# Bauble.net
KiCad netlist of a schematic drawn in EAGLE
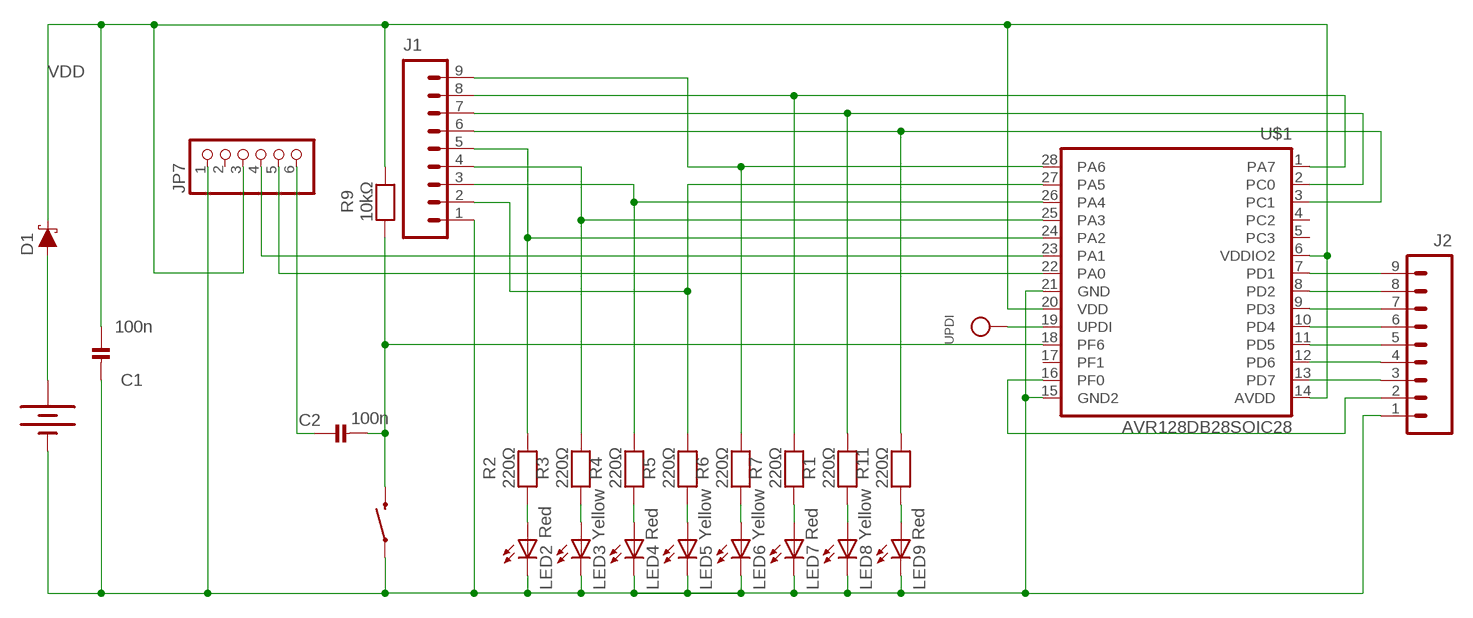
[diagram p0: schematic, sheet 1]

(export (version "E")
  (design (tool "Eeschema 10.0.6"))
  (components
    (comp (ref "BAT2")
      (value "20mm coincell")
      (footprint "eagle-import:BATTCON_20MM_4LEGS")
      (libsource (lib "eagle-import") (part "BATTERY20MM_4LEGS"))
    )
    (comp (ref "C1")
      (value "100n")
      (footprint "eagle-import:_0805MP")
      (libsource (lib "eagle-import") (part "CAP_CERAMIC_0805MP"))
    )
    (comp (ref "C2")
      (value "100n")
      (footprint "eagle-import:_0805MP")
      (libsource (lib "eagle-import") (part "CAP_CERAMIC_0805MP"))
    )
    (comp (ref "D1")
      (value "3A/10V/280mV")
      (footprint "eagle-import:SOD-323")
      (libsource (lib "eagle-import") (part "DIODE-SCHOTTKY-BAT60A"))
    )
    (comp (ref "J1")
      (value "M82MM")
      (footprint "eagle-import:1X10-2MM")
      (libsource (lib "eagle-import") (part "M82MM"))
    )
    (comp (ref "J2")
      (value "M82MM")
      (footprint "eagle-import:1X10-2MM")
      (libsource (lib "eagle-import") (part "M82MM"))
    )
    (comp (ref "JP7")
      (value "HEADER-1X6ROUND")
      (footprint "eagle-import:1X06_ROUND")
      (libsource (lib "eagle-import") (part "HEADER-1X6ROUND"))
    )
    (comp (ref "LED2")
      (value "Red")
      (footprint "eagle-import:CHIPLED_0805")
      (libsource (lib "eagle-import") (part "LEDCHIPLED_0805"))
    )
    (comp (ref "LED3")
      (value "Yellow")
      (footprint "eagle-import:CHIPLED_0805")
      (libsource (lib "eagle-import") (part "LEDCHIPLED_0805"))
    )
    (comp (ref "LED4")
      (value "Red")
      (footprint "eagle-import:CHIPLED_0805")
      (libsource (lib "eagle-import") (part "LEDCHIPLED_0805"))
    )
    (comp (ref "LED5")
      (value "Yellow")
      (footprint "eagle-import:CHIPLED_0805")
      (libsource (lib "eagle-import") (part "LEDCHIPLED_0805"))
    )
    (comp (ref "LED6")
      (value "Yellow")
      (footprint "eagle-import:CHIPLED_0805")
      (libsource (lib "eagle-import") (part "LEDCHIPLED_0805"))
    )
    (comp (ref "LED7")
      (value "Red")
      (footprint "eagle-import:CHIPLED_0805")
      (libsource (lib "eagle-import") (part "LEDCHIPLED_0805"))
    )
    (comp (ref "LED8")
      (value "Yellow")
      (footprint "eagle-import:CHIPLED_0805")
      (libsource (lib "eagle-import") (part "LEDCHIPLED_0805"))
    )
    (comp (ref "LED9")
      (value "Red")
      (footprint "eagle-import:CHIPLED_0805")
      (libsource (lib "eagle-import") (part "LEDCHIPLED_0805"))
    )
    (comp (ref "R1")
      (value "220Ω")
      (footprint "eagle-import:_0805MP")
      (libsource (lib "eagle-import") (part "RESISTOR_0805MP"))
    )
    (comp (ref "R2")
      (value "220Ω")
      (footprint "eagle-import:_0805MP")
      (libsource (lib "eagle-import") (part "RESISTOR_0805MP"))
    )
    (comp (ref "R3")
      (value "220Ω")
      (footprint "eagle-import:_0805MP")
      (libsource (lib "eagle-import") (part "RESISTOR_0805MP"))
    )
    (comp (ref "R4")
      (value "220Ω")
      (footprint "eagle-import:_0805MP")
      (libsource (lib "eagle-import") (part "RESISTOR_0805MP"))
    )
    (comp (ref "R5")
      (value "220Ω")
      (footprint "eagle-import:_0805MP")
      (libsource (lib "eagle-import") (part "RESISTOR_0805MP"))
    )
    (comp (ref "R6")
      (value "220Ω")
      (footprint "eagle-import:_0805MP")
      (libsource (lib "eagle-import") (part "RESISTOR_0805MP"))
    )
    (comp (ref "R7")
      (value "220Ω")
      (footprint "eagle-import:_0805MP")
      (libsource (lib "eagle-import") (part "RESISTOR_0805MP"))
    )
    (comp (ref "R9")
      (value "10kΩ")
      (footprint "eagle-import:_0805MP")
      (libsource (lib "eagle-import") (part "RESISTOR_0805MP"))
    )
    (comp (ref "R11")
      (value "220Ω")
      (footprint "eagle-import:_0805MP")
      (libsource (lib "eagle-import") (part "RESISTOR_0805MP"))
    )
    (comp (ref "S2")
      (value "SWITCH-MOMENTARY-2SMD")
      (footprint "eagle-import:TACTILE-SWITCH-SMD")
      (libsource (lib "eagle-import") (part "SWITCH-MOMENTARY-2SMD"))
    )
    (comp (ref "U$1")
      (value "AVR128DB28SOIC28")
      (footprint "eagle-import:SO-28W")
      (libsource (lib "eagle-import") (part "AVR128DB28SOIC28"))
    )
    (comp (ref "UPDI")
      (value "TESTPOINTROUND1MM")
      (footprint "eagle-import:TESTPOINT_ROUND_1MM")
      (libsource (lib "eagle-import") (part "TESTPOINTROUND1MM"))
    )
  )
  (nets
    (net (code "1") (name "Net-(BAT2-+-PadPOSITIVE@1)") (class "Default")
      (node (ref "BAT2") (pin "POSITIVE@1") (pinfunction "+_POSITIVE@1") (pintype "power_in"))
      (node (ref "BAT2") (pin "POSITIVE@2") (pinfunction "+_POSITIVE@2") (pintype "power_in"))
      (node (ref "BAT2") (pin "POSITIVE@3") (pinfunction "+_POSITIVE@3") (pintype "power_in"))
      (node (ref "BAT2") (pin "POSITIVE@4") (pinfunction "+_POSITIVE@4") (pintype "power_in"))
      (node (ref "D1") (pin "A") (pinfunction "A_A") (pintype "passive"))
    )
    (net (code "2") (name "Net-(BAT2--)") (class "Default")
      (node (ref "BAT2") (pin "NEGATIVE") (pinfunction "-_NEGATIVE") (pintype "power_in"))
      (node (ref "C1") (pin "2") (pinfunction "P$2_2") (pintype "passive"))
      (node (ref "J1") (pin "1") (pinfunction "1_1") (pintype "passive"))
      (node (ref "J2") (pin "1") (pinfunction "1_1") (pintype "passive"))
      (node (ref "JP7") (pin "1") (pinfunction "1_1") (pintype "passive"))
      (node (ref "LED2") (pin "C") (pinfunction "C_C") (pintype "passive"))
      (node (ref "LED3") (pin "C") (pinfunction "C_C") (pintype "passive"))
      (node (ref "LED4") (pin "C") (pinfunction "C_C") (pintype "passive"))
      (node (ref "LED5") (pin "C") (pinfunction "C_C") (pintype "passive"))
      (node (ref "LED6") (pin "C") (pinfunction "C_C") (pintype "passive"))
      (node (ref "LED7") (pin "C") (pinfunction "C_C") (pintype "passive"))
      (node (ref "LED8") (pin "C") (pinfunction "C_C") (pintype "passive"))
      (node (ref "LED9") (pin "C") (pinfunction "C_C") (pintype "passive"))
      (node (ref "S2") (pin "1") (pinfunction "1_1") (pintype "passive"))
      (node (ref "U$1") (pin "15") (pinfunction "GND2_15") (pintype "bidirectional"))
      (node (ref "U$1") (pin "21") (pinfunction "GND_21") (pintype "bidirectional"))
    )
    (net (code "3") (name "Net-(C2-P$1)") (class "Default")
      (node (ref "C2") (pin "1") (pinfunction "P$1_1") (pintype "passive"))
      (node (ref "JP7") (pin "6") (pinfunction "6_6") (pintype "passive"))
    )
    (net (code "4") (name "Net-(C2-P$2)") (class "Default")
      (node (ref "C2") (pin "2") (pinfunction "P$2_2") (pintype "passive"))
      (node (ref "R9") (pin "1") (pinfunction "1_1") (pintype "passive"))
      (node (ref "S2") (pin "3") (pinfunction "2_3") (pintype "passive"))
      (node (ref "U$1") (pin "18") (pinfunction "PF6_18") (pintype "input"))
    )
    (net (code "5") (name "Net-(LED2-PadA)") (class "Default")
      (node (ref "LED2") (pin "A") (pinfunction "A_A") (pintype "passive"))
      (node (ref "R2") (pin "1") (pinfunction "1_1") (pintype "passive"))
    )
    (net (code "6") (name "Net-(LED3-PadA)") (class "Default")
      (node (ref "LED3") (pin "A") (pinfunction "A_A") (pintype "passive"))
      (node (ref "R3") (pin "1") (pinfunction "1_1") (pintype "passive"))
    )
    (net (code "7") (name "Net-(LED4-PadA)") (class "Default")
      (node (ref "LED4") (pin "A") (pinfunction "A_A") (pintype "passive"))
      (node (ref "R4") (pin "1") (pinfunction "1_1") (pintype "passive"))
    )
    (net (code "8") (name "Net-(LED5-PadA)") (class "Default")
      (node (ref "LED5") (pin "A") (pinfunction "A_A") (pintype "passive"))
      (node (ref "R5") (pin "1") (pinfunction "1_1") (pintype "passive"))
    )
    (net (code "9") (name "Net-(LED6-PadA)") (class "Default")
      (node (ref "LED6") (pin "A") (pinfunction "A_A") (pintype "passive"))
      (node (ref "R6") (pin "1") (pinfunction "1_1") (pintype "passive"))
    )
    (net (code "10") (name "Net-(LED7-PadA)") (class "Default")
      (node (ref "LED7") (pin "A") (pinfunction "A_A") (pintype "passive"))
      (node (ref "R7") (pin "1") (pinfunction "1_1") (pintype "passive"))
    )
    (net (code "11") (name "Net-(LED8-PadA)") (class "Default")
      (node (ref "LED8") (pin "A") (pinfunction "A_A") (pintype "passive"))
      (node (ref "R1") (pin "1") (pinfunction "1_1") (pintype "passive"))
    )
    (net (code "12") (name "Net-(LED9-PadA)") (class "Default")
      (node (ref "LED9") (pin "A") (pinfunction "A_A") (pintype "passive"))
      (node (ref "R11") (pin "1") (pinfunction "1_1") (pintype "passive"))
    )
    (net (code "13") (name "Net-(U$1-PA0)") (class "Default")
      (node (ref "JP7") (pin "5") (pinfunction "5_5") (pintype "passive"))
      (node (ref "U$1") (pin "22") (pinfunction "PA0_22") (pintype "bidirectional"))
    )
    (net (code "14") (name "Net-(U$1-PA1)") (class "Default")
      (node (ref "JP7") (pin "4") (pinfunction "4_4") (pintype "passive"))
      (node (ref "U$1") (pin "23") (pinfunction "PA1_23") (pintype "bidirectional"))
    )
    (net (code "15") (name "Net-(U$1-PA2)") (class "Default")
      (node (ref "J1") (pin "5") (pinfunction "5_5") (pintype "passive"))
      (node (ref "R2") (pin "2") (pinfunction "2_2") (pintype "passive"))
      (node (ref "U$1") (pin "24") (pinfunction "PA2_24") (pintype "bidirectional"))
    )
    (net (code "16") (name "Net-(U$1-PA3)") (class "Default")
      (node (ref "J1") (pin "4") (pinfunction "4_4") (pintype "passive"))
      (node (ref "R3") (pin "2") (pinfunction "2_2") (pintype "passive"))
      (node (ref "U$1") (pin "25") (pinfunction "PA3_25") (pintype "bidirectional"))
    )
    (net (code "17") (name "Net-(U$1-PA4)") (class "Default")
      (node (ref "J1") (pin "3") (pinfunction "3_3") (pintype "passive"))
      (node (ref "R4") (pin "2") (pinfunction "2_2") (pintype "passive"))
      (node (ref "U$1") (pin "26") (pinfunction "PA4_26") (pintype "bidirectional"))
    )
    (net (code "18") (name "Net-(U$1-PA5)") (class "Default")
      (node (ref "J1") (pin "2") (pinfunction "2_2") (pintype "passive"))
      (node (ref "R5") (pin "2") (pinfunction "2_2") (pintype "passive"))
      (node (ref "U$1") (pin "27") (pinfunction "PA5_27") (pintype "bidirectional"))
    )
    (net (code "19") (name "Net-(U$1-PA6)") (class "Default")
      (node (ref "J1") (pin "9") (pinfunction "9_9") (pintype "passive"))
      (node (ref "R6") (pin "2") (pinfunction "2_2") (pintype "passive"))
      (node (ref "U$1") (pin "28") (pinfunction "PA6_28") (pintype "bidirectional"))
    )
    (net (code "20") (name "Net-(U$1-PA7)") (class "Default")
      (node (ref "J1") (pin "8") (pinfunction "8_8") (pintype "passive"))
      (node (ref "R7") (pin "2") (pinfunction "2_2") (pintype "passive"))
      (node (ref "U$1") (pin "1") (pinfunction "PA7_1") (pintype "bidirectional"))
    )
    (net (code "21") (name "Net-(U$1-PC0)") (class "Default")
      (node (ref "J1") (pin "7") (pinfunction "7_7") (pintype "passive"))
      (node (ref "R1") (pin "2") (pinfunction "2_2") (pintype "passive"))
      (node (ref "U$1") (pin "2") (pinfunction "PC0_2") (pintype "bidirectional"))
    )
    (net (code "22") (name "Net-(U$1-PC1)") (class "Default")
      (node (ref "J1") (pin "6") (pinfunction "6_6") (pintype "passive"))
      (node (ref "R11") (pin "2") (pinfunction "2_2") (pintype "passive"))
      (node (ref "U$1") (pin "3") (pinfunction "PC1_3") (pintype "bidirectional"))
    )
    (net (code "23") (name "Net-(U$1-PD1)") (class "Default")
      (node (ref "J2") (pin "9") (pinfunction "9_9") (pintype "passive"))
      (node (ref "U$1") (pin "7") (pinfunction "PD1_7") (pintype "bidirectional"))
    )
    (net (code "24") (name "Net-(U$1-PD2)") (class "Default")
      (node (ref "J2") (pin "8") (pinfunction "8_8") (pintype "passive"))
      (node (ref "U$1") (pin "8") (pinfunction "PD2_8") (pintype "power_in"))
    )
    (net (code "25") (name "Net-(U$1-PD3)") (class "Default")
      (node (ref "J2") (pin "7") (pinfunction "7_7") (pintype "passive"))
      (node (ref "U$1") (pin "9") (pinfunction "PD3_9") (pintype "bidirectional"))
    )
    (net (code "26") (name "Net-(U$1-PD4)") (class "Default")
      (node (ref "J2") (pin "6") (pinfunction "6_6") (pintype "passive"))
      (node (ref "U$1") (pin "10") (pinfunction "PD4_10") (pintype "bidirectional"))
    )
    (net (code "27") (name "Net-(U$1-PD5)") (class "Default")
      (node (ref "J2") (pin "5") (pinfunction "5_5") (pintype "passive"))
      (node (ref "U$1") (pin "11") (pinfunction "PD5_11") (pintype "bidirectional"))
    )
    (net (code "28") (name "Net-(U$1-PD6)") (class "Default")
      (node (ref "J2") (pin "4") (pinfunction "4_4") (pintype "passive"))
      (node (ref "U$1") (pin "12") (pinfunction "PD6_12") (pintype "bidirectional"))
    )
    (net (code "29") (name "Net-(U$1-PD7)") (class "Default")
      (node (ref "J2") (pin "3") (pinfunction "3_3") (pintype "passive"))
      (node (ref "U$1") (pin "13") (pinfunction "PD7_13") (pintype "bidirectional"))
    )
    (net (code "30") (name "Net-(U$1-PF0)") (class "Default")
      (node (ref "J2") (pin "2") (pinfunction "2_2") (pintype "passive"))
      (node (ref "U$1") (pin "16") (pinfunction "PF0_16") (pintype "bidirectional"))
    )
    (net (code "31") (name "Net-(U$1-UPDI)") (class "Default")
      (node (ref "U$1") (pin "19") (pinfunction "UPDI_19") (pintype "power_in"))
      (node (ref "UPDI") (pin "P$1") (pinfunction "P$1_P$1") (pintype "bidirectional"))
    )
    (net (code "32") (name "VDD") (class "Default")
      (node (ref "C1") (pin "1") (pinfunction "P$1_1") (pintype "passive"))
      (node (ref "D1") (pin "C") (pinfunction "C_C") (pintype "passive"))
      (node (ref "JP7") (pin "3") (pinfunction "3_3") (pintype "passive"))
      (node (ref "R9") (pin "2") (pinfunction "2_2") (pintype "passive"))
      (node (ref "U$1") (pin "14") (pinfunction "AVDD_14") (pintype "bidirectional"))
      (node (ref "U$1") (pin "20") (pinfunction "VDD_20") (pintype "power_in"))
      (node (ref "U$1") (pin "6") (pinfunction "VDDIO2_6") (pintype "bidirectional"))
    )
    (net (code "33") (name "unconnected-(JP7-Pad2)") (class "Default")
      (node (ref "JP7") (pin "2") (pinfunction "2_2") (pintype "passive"))
    )
    (net (code "34") (name "unconnected-(U$1-PC2-Pad4)") (class "Default")
      (node (ref "U$1") (pin "4") (pinfunction "PC2_4") (pintype "bidirectional"))
    )
    (net (code "35") (name "unconnected-(U$1-PC3-Pad5)") (class "Default")
      (node (ref "U$1") (pin "5") (pinfunction "PC3_5") (pintype "bidirectional"))
    )
    (net (code "36") (name "unconnected-(U$1-PF1-Pad17)") (class "Default")
      (node (ref "U$1") (pin "17") (pinfunction "PF1_17") (pintype "bidirectional"))
    )
  )
)
